# Clock_Led_7_thanh_Huynh_Tan_Cuong.net
KiCad netlist of a schematic drawn in Altium Designer
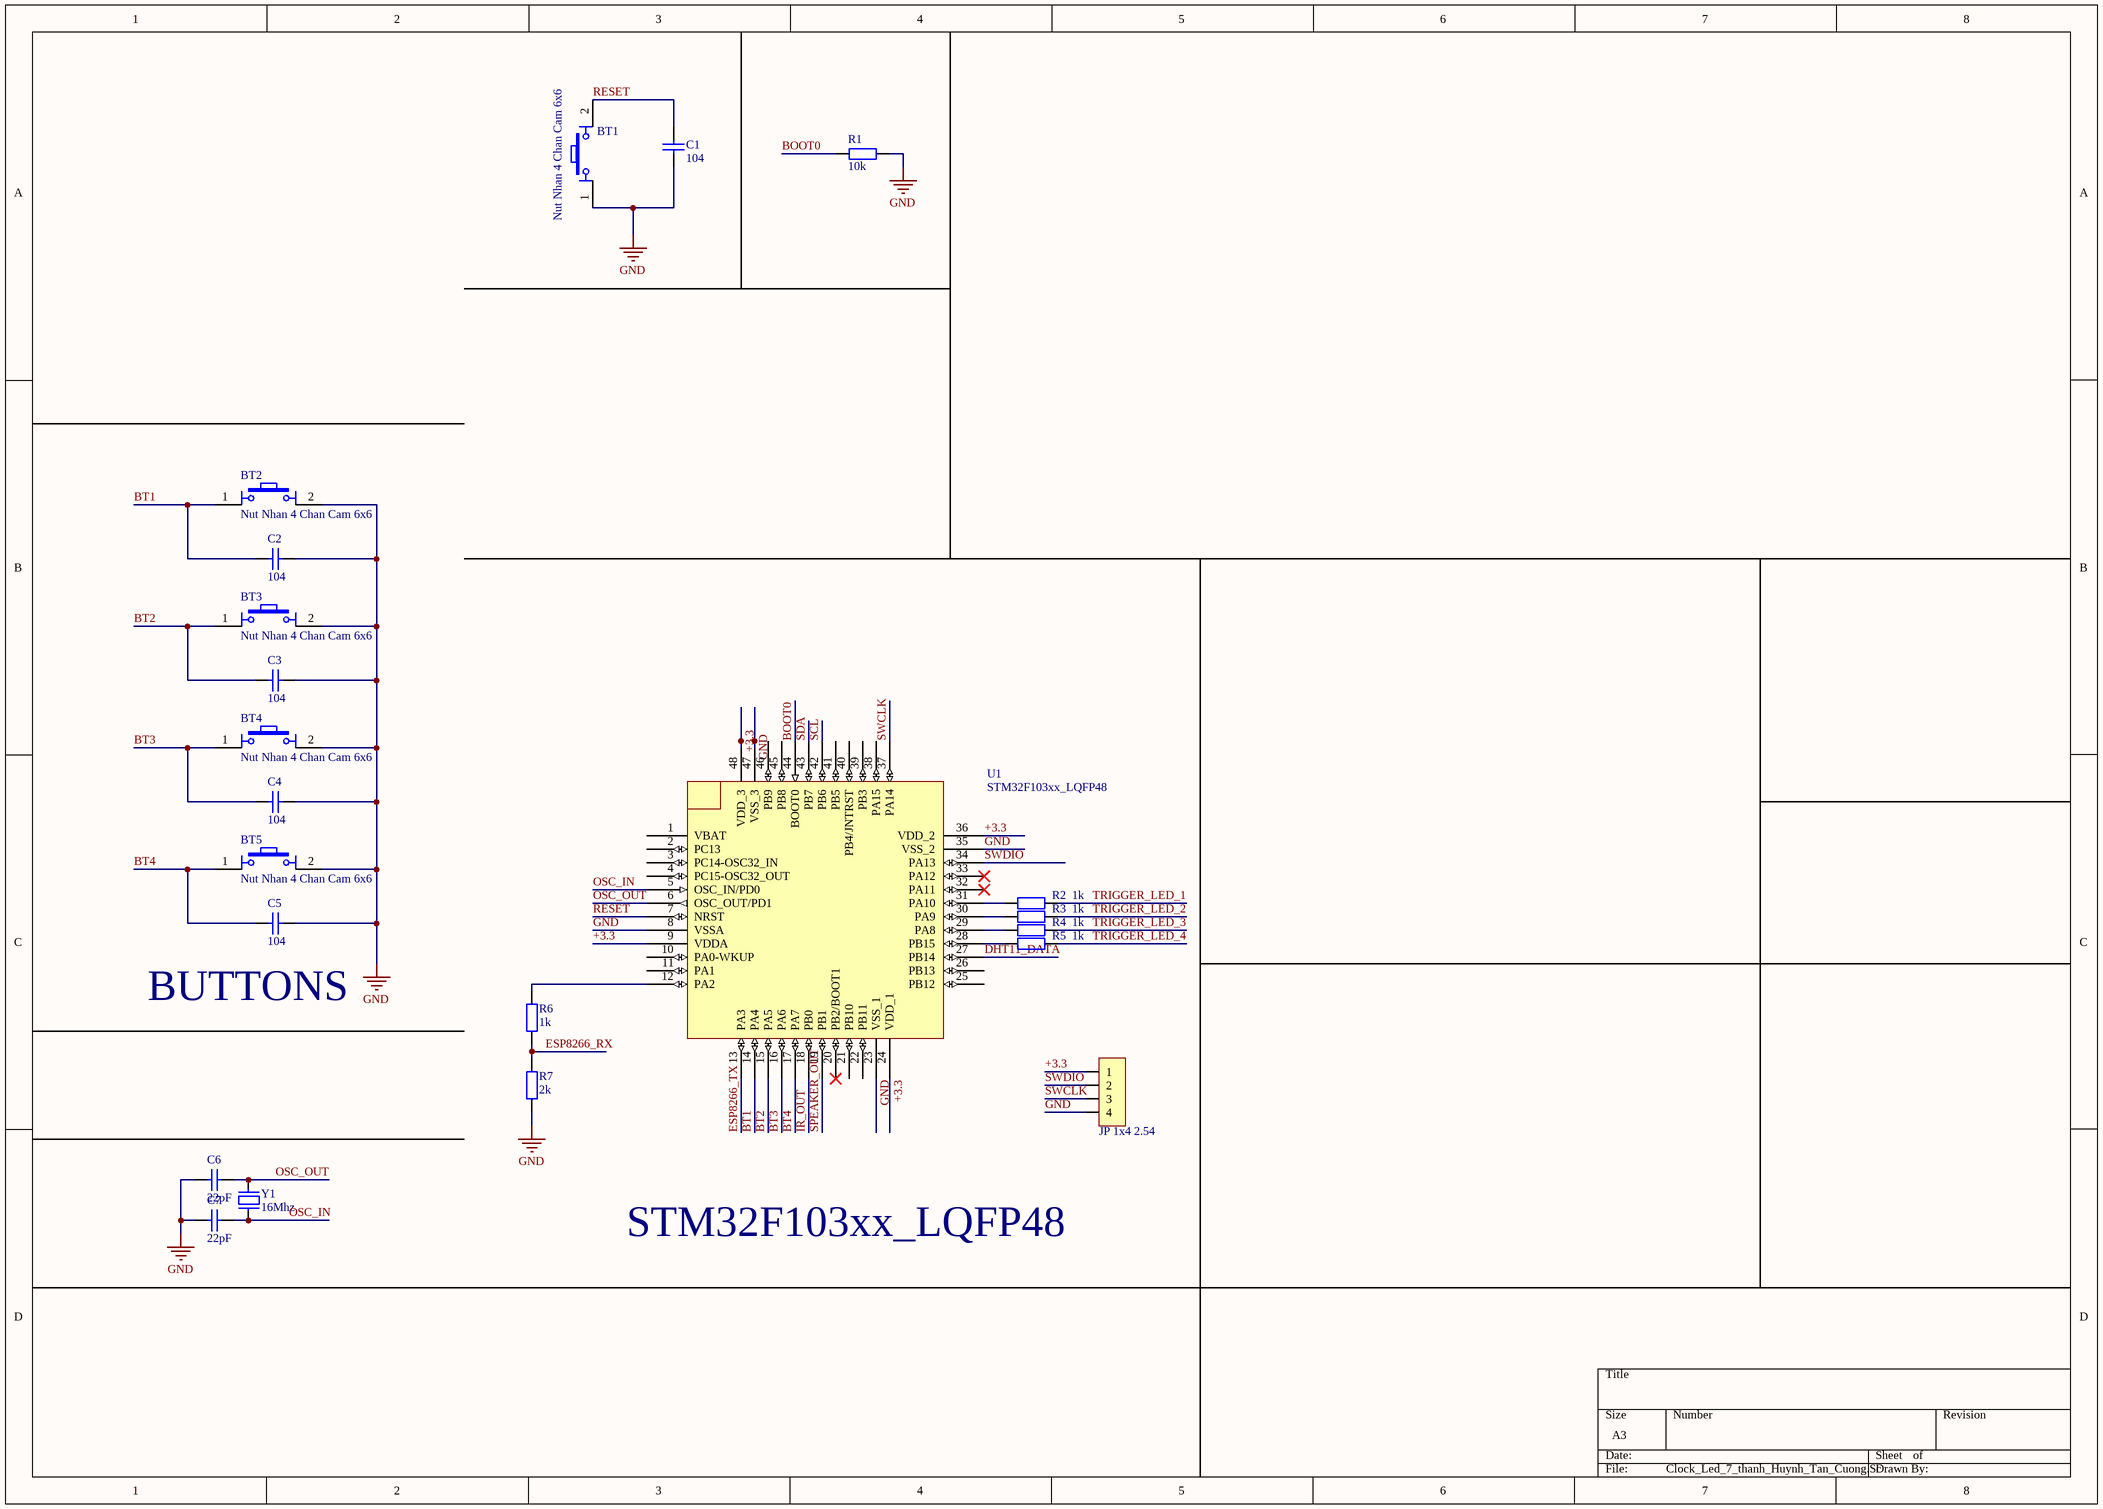
[diagram p0: Clock_Led_7_thanh_Huynh_Tan_Cuong.SchDoc]

(export (version "E")
  (design (tool "Eeschema 10.0.6"))
  (components
    (comp (ref "BT1")
      (value "Nut Nhan 4 Chan Cam 6x6")
      (footprint "Nut Nhan 4 Chan Cam 6x6")
      (description "Nut Nhan 4 Chan 6x6mm")
      (libsource (lib "") (part "Nut Nhan 4 Chan Cam 6x6_1"))
    )
    (comp (ref "BT2")
      (value "Nut Nhan 4 Chan Cam 6x6")
      (footprint "Nut Nhan 4 Chan Cam 6x6")
      (description "Nut Nhan 4 Chan 6x6mm")
      (libsource (lib "Altium_Lib_by_KhueNguyenCreator") (part "Nut Nhan 4 Chan Cam 6x6"))
    )
    (comp (ref "BT3")
      (value "Nut Nhan 4 Chan Cam 6x6")
      (footprint "Nut Nhan 4 Chan Cam 6x6")
      (description "Nut Nhan 4 Chan 6x6mm")
      (libsource (lib "Altium_Lib_by_KhueNguyenCreator") (part "Nut Nhan 4 Chan Cam 6x6"))
    )
    (comp (ref "BT4")
      (value "Nut Nhan 4 Chan Cam 6x6")
      (footprint "Nut Nhan 4 Chan Cam 6x6")
      (description "Nut Nhan 4 Chan 6x6mm")
      (libsource (lib "Altium_Lib_by_KhueNguyenCreator") (part "Nut Nhan 4 Chan Cam 6x6"))
    )
    (comp (ref "BT5")
      (value "Nut Nhan 4 Chan Cam 6x6")
      (footprint "Nut Nhan 4 Chan Cam 6x6")
      (description "Nut Nhan 4 Chan 6x6mm")
      (libsource (lib "Altium_Lib_by_KhueNguyenCreator") (part "Nut Nhan 4 Chan Cam 6x6"))
    )
    (comp (ref "C1")
      (value "104")
      (footprint "tu 0603")
      (description "Dán")
      (libsource (lib "Altium_Lib_by_KhueNguyenCreator") (part "Tu 0603 104 50V 10%"))
    )
    (comp (ref "C2")
      (value "104")
      (footprint "tu 0603")
      (description "Dán")
      (libsource (lib "Altium_Lib_by_KhueNguyenCreator") (part "Tu 0603 104 50V 10%"))
    )
    (comp (ref "C3")
      (value "104")
      (footprint "tu 0603")
      (description "Dán")
      (libsource (lib "Altium_Lib_by_KhueNguyenCreator") (part "Tu 0603 104 50V 10%"))
    )
    (comp (ref "C4")
      (value "104")
      (footprint "tu 0603")
      (description "Dán")
      (libsource (lib "Altium_Lib_by_KhueNguyenCreator") (part "Tu 0603 104 50V 10%"))
    )
    (comp (ref "C5")
      (value "104")
      (footprint "tu 0603")
      (description "Dán")
      (libsource (lib "Altium_Lib_by_KhueNguyenCreator") (part "Tu 0603 104 50V 10%"))
    )
    (comp (ref "C6")
      (value "22pF")
      (footprint "tu 0603")
      (description "Dán")
      (libsource (lib "Altium_Lib_by_KhueNguyenCreator") (part "Tu 0603 22pF 50V 10%"))
    )
    (comp (ref "C7")
      (value "22pF")
      (footprint "tu 0603")
      (description "Dán")
      (libsource (lib "Altium_Lib_by_KhueNguyenCreator") (part "Tu 0603 22pF 50V 10%"))
    )
    (comp (ref "JP1")
      (value "JP 1x4 2.54")
      (footprint "JP 1x4 DC")
      (description "Cắm")
      (libsource (lib "Altium_Lib_by_KhueNguyenCreator") (part "JP 1x4 2.54 Duc Cong"))
    )
    (comp (ref "R1")
      (value "10k")
      (footprint "tro smd 0603")
      (description "Dán")
      (libsource (lib "Altium_Lib_by_KhueNguyenCreator") (part "Tro 0603 1% 10k"))
    )
    (comp (ref "R2")
      (value "1k")
      (footprint "tro smd 0603")
      (description "Dán")
      (libsource (lib "Altium_Lib_by_KhueNguyenCreator") (part "Tro 0603 1% 1k"))
    )
    (comp (ref "R3")
      (value "1k")
      (footprint "tro smd 0603")
      (description "Dán")
      (libsource (lib "Altium_Lib_by_KhueNguyenCreator") (part "Tro 0603 1% 1k"))
    )
    (comp (ref "R4")
      (value "1k")
      (footprint "tro smd 0603")
      (description "Dán")
      (libsource (lib "Altium_Lib_by_KhueNguyenCreator") (part "Tro 0603 1% 1k"))
    )
    (comp (ref "R5")
      (value "1k")
      (footprint "tro smd 0603")
      (description "Dán")
      (libsource (lib "Altium_Lib_by_KhueNguyenCreator") (part "Tro 0603 1% 1k"))
    )
    (comp (ref "R6")
      (value "1k")
      (footprint "tro smd 0603")
      (description "Dán")
      (libsource (lib "Altium_Lib_by_KhueNguyenCreator") (part "Tro 0603 1% 1k"))
    )
    (comp (ref "R7")
      (value "2k")
      (footprint "tro smd 0603")
      (description "Dán")
      (libsource (lib "Altium_Lib_by_KhueNguyenCreator") (part "Tro 0603 5% 2k"))
    )
    (comp (ref "U1")
      (value "STM32F103xx_LQFP48")
      (footprint "STM32_LQPF48")
      (fields (field (name "PUBLISHER") "Altium Limited"))
      (libsource (lib "Altium_Lib_by_KhueNguyenCreator") (part "STM32F103xx_LQFP48"))
    )
    (comp (ref "Y1")
      (value "16Mhz")
      (footprint "Thach Anh 2 chan SMD")
      (description "Crystal For all Crystal 2pin.")
      (libsource (lib "Altium_Lib_by_KhueNguyenCreator") (part "Thach Anh 2 chan SMD"))
    )
  )
  (nets
    (net (code "1") (name "/+3.3") (class "Default")
      (node (ref "JP1") (pin "1") (pinfunction "1_1") (pintype "passive"))
      (node (ref "U1") (pin "24") (pinfunction "VDD_1_24") (pintype "power_in"))
      (node (ref "U1") (pin "36") (pinfunction "VDD_2_36") (pintype "power_in"))
      (node (ref "U1") (pin "48") (pinfunction "VDD_3_48") (pintype "power_in"))
      (node (ref "U1") (pin "9") (pinfunction "VDDA_9") (pintype "power_in"))
    )
    (net (code "2") (name "/BOOT0") (class "Default")
      (node (ref "R1") (pin "1") (pinfunction "1_1") (pintype "passive"))
      (node (ref "U1") (pin "44") (pinfunction "BOOT0_44") (pintype "input"))
    )
    (net (code "3") (name "/BT1") (class "Default")
      (node (ref "BT2") (pin "1") (pintype "passive"))
      (node (ref "C2") (pin "1") (pinfunction "1_1") (pintype "passive"))
      (node (ref "U1") (pin "14") (pinfunction "PA4_14") (pintype "bidirectional"))
    )
    (net (code "4") (name "/BT2") (class "Default")
      (node (ref "BT3") (pin "1") (pintype "passive"))
      (node (ref "C3") (pin "1") (pinfunction "1_1") (pintype "passive"))
      (node (ref "U1") (pin "15") (pinfunction "PA5_15") (pintype "bidirectional"))
    )
    (net (code "5") (name "/BT3") (class "Default")
      (node (ref "BT4") (pin "1") (pintype "passive"))
      (node (ref "C4") (pin "1") (pinfunction "1_1") (pintype "passive"))
      (node (ref "U1") (pin "16") (pinfunction "PA6_16") (pintype "bidirectional"))
    )
    (net (code "6") (name "/BT4") (class "Default")
      (node (ref "BT5") (pin "1") (pintype "passive"))
      (node (ref "C5") (pin "1") (pinfunction "1_1") (pintype "passive"))
      (node (ref "U1") (pin "17") (pinfunction "PA7_17") (pintype "bidirectional"))
    )
    (net (code "7") (name "/DHT11_DATA") (class "Default")
      (node (ref "U1") (pin "27") (pinfunction "PB14_27") (pintype "bidirectional"))
    )
    (net (code "8") (name "/ESP8266_RX") (class "Default")
      (node (ref "R6") (pin "1") (pinfunction "1_1") (pintype "passive"))
      (node (ref "R7") (pin "2") (pinfunction "2_2") (pintype "passive"))
    )
    (net (code "9") (name "/ESP8266_TX") (class "Default")
      (node (ref "U1") (pin "13") (pinfunction "PA3_13") (pintype "bidirectional"))
    )
    (net (code "10") (name "/IR_OUT") (class "Default")
      (node (ref "U1") (pin "18") (pinfunction "PB0_18") (pintype "bidirectional"))
    )
    (net (code "11") (name "/OSC_IN") (class "Default")
      (node (ref "C7") (pin "1") (pinfunction "1_1") (pintype "passive"))
      (node (ref "U1") (pin "5") (pinfunction "OSC_IN/PD0_5") (pintype "input"))
      (node (ref "Y1") (pin "1") (pinfunction "1_1") (pintype "passive"))
    )
    (net (code "12") (name "/OSC_OUT") (class "Default")
      (node (ref "C6") (pin "1") (pinfunction "1_1") (pintype "passive"))
      (node (ref "U1") (pin "6") (pinfunction "OSC_OUT/PD1_6") (pintype "output"))
      (node (ref "Y1") (pin "2") (pinfunction "2_2") (pintype "passive"))
    )
    (net (code "13") (name "/RESET") (class "Default")
      (node (ref "BT1") (pin "2") (pintype "passive"))
      (node (ref "C1") (pin "1") (pinfunction "1_1") (pintype "passive"))
      (node (ref "U1") (pin "7") (pinfunction "NRST_7") (pintype "bidirectional"))
    )
    (net (code "14") (name "/SCL") (class "Default")
      (node (ref "U1") (pin "42") (pinfunction "PB6_42") (pintype "bidirectional"))
    )
    (net (code "15") (name "/SDA") (class "Default")
      (node (ref "U1") (pin "43") (pinfunction "PB7_43") (pintype "bidirectional"))
    )
    (net (code "16") (name "/SPEAKER_OUT") (class "Default")
      (node (ref "U1") (pin "19") (pinfunction "PB1_19") (pintype "bidirectional"))
    )
    (net (code "17") (name "/SWCLK") (class "Default")
      (node (ref "JP1") (pin "3") (pinfunction "3_3") (pintype "passive"))
      (node (ref "U1") (pin "37") (pinfunction "PA14_37") (pintype "bidirectional"))
    )
    (net (code "18") (name "/SWDIO") (class "Default")
      (node (ref "JP1") (pin "2") (pinfunction "2_2") (pintype "passive"))
      (node (ref "U1") (pin "34") (pinfunction "PA13_34") (pintype "bidirectional"))
    )
    (net (code "19") (name "/TRIGGER_LED_1") (class "Default")
      (node (ref "R2") (pin "2") (pinfunction "2_2") (pintype "passive"))
    )
    (net (code "20") (name "/TRIGGER_LED_2") (class "Default")
      (node (ref "R3") (pin "2") (pinfunction "2_2") (pintype "passive"))
    )
    (net (code "21") (name "/TRIGGER_LED_3") (class "Default")
      (node (ref "R4") (pin "2") (pinfunction "2_2") (pintype "passive"))
    )
    (net (code "22") (name "/TRIGGER_LED_4") (class "Default")
      (node (ref "R5") (pin "2") (pinfunction "2_2") (pintype "passive"))
    )
    (net (code "23") (name "GND") (class "Default")
      (node (ref "BT1") (pin "1") (pintype "passive"))
      (node (ref "BT2") (pin "2") (pintype "passive"))
      (node (ref "BT3") (pin "2") (pintype "passive"))
      (node (ref "BT4") (pin "2") (pintype "passive"))
      (node (ref "BT5") (pin "2") (pintype "passive"))
      (node (ref "C1") (pin "2") (pinfunction "2_2") (pintype "passive"))
      (node (ref "C2") (pin "2") (pinfunction "2_2") (pintype "passive"))
      (node (ref "C3") (pin "2") (pinfunction "2_2") (pintype "passive"))
      (node (ref "C4") (pin "2") (pinfunction "2_2") (pintype "passive"))
      (node (ref "C5") (pin "2") (pinfunction "2_2") (pintype "passive"))
      (node (ref "C6") (pin "2") (pinfunction "2_2") (pintype "passive"))
      (node (ref "C7") (pin "2") (pinfunction "2_2") (pintype "passive"))
      (node (ref "JP1") (pin "4") (pinfunction "4_4") (pintype "passive"))
      (node (ref "R1") (pin "2") (pinfunction "2_2") (pintype "passive"))
      (node (ref "R7") (pin "1") (pinfunction "1_1") (pintype "passive"))
      (node (ref "U1") (pin "23") (pinfunction "VSS_1_23") (pintype "power_in"))
      (node (ref "U1") (pin "35") (pinfunction "VSS_2_35") (pintype "power_in"))
      (node (ref "U1") (pin "47") (pinfunction "VSS_3_47") (pintype "power_in"))
      (node (ref "U1") (pin "8") (pinfunction "VSSA_8") (pintype "power_in"))
    )
    (net (code "24") (name "Net-(U1-PA2)") (class "Default")
      (node (ref "R6") (pin "2") (pinfunction "2_2") (pintype "passive"))
      (node (ref "U1") (pin "12") (pinfunction "PA2_12") (pintype "bidirectional"))
    )
    (net (code "25") (name "Net-(U1-PA8)") (class "Default")
      (node (ref "R4") (pin "1") (pinfunction "1_1") (pintype "passive"))
      (node (ref "U1") (pin "29") (pinfunction "PA8_29") (pintype "bidirectional"))
    )
    (net (code "26") (name "Net-(U1-PA9)") (class "Default")
      (node (ref "R3") (pin "1") (pinfunction "1_1") (pintype "passive"))
      (node (ref "U1") (pin "30") (pinfunction "PA9_30") (pintype "bidirectional"))
    )
    (net (code "27") (name "Net-(U1-PA10)") (class "Default")
      (node (ref "R2") (pin "1") (pinfunction "1_1") (pintype "passive"))
      (node (ref "U1") (pin "31") (pinfunction "PA10_31") (pintype "bidirectional"))
    )
    (net (code "28") (name "Net-(U1-PB15)") (class "Default")
      (node (ref "R5") (pin "1") (pinfunction "1_1") (pintype "passive"))
      (node (ref "U1") (pin "28") (pinfunction "PB15_28") (pintype "bidirectional"))
    )
    (net (code "29") (name "unconnected-(U1-PA0-WKUP-Pad10)") (class "Default")
      (node (ref "U1") (pin "10") (pinfunction "PA0-WKUP_10") (pintype "bidirectional"))
    )
    (net (code "30") (name "unconnected-(U1-PA1-Pad11)") (class "Default")
      (node (ref "U1") (pin "11") (pinfunction "PA1_11") (pintype "bidirectional"))
    )
    (net (code "31") (name "unconnected-(U1-PA11-Pad32)") (class "Default")
      (node (ref "U1") (pin "32") (pinfunction "PA11_32") (pintype "bidirectional+no_connect"))
    )
    (net (code "32") (name "unconnected-(U1-PA12-Pad33)") (class "Default")
      (node (ref "U1") (pin "33") (pinfunction "PA12_33") (pintype "bidirectional+no_connect"))
    )
    (net (code "33") (name "unconnected-(U1-PA15-Pad38)") (class "Default")
      (node (ref "U1") (pin "38") (pinfunction "PA15_38") (pintype "bidirectional"))
    )
    (net (code "34") (name "unconnected-(U1-PB2{slash}BOOT1-Pad20)") (class "Default")
      (node (ref "U1") (pin "20") (pinfunction "PB2/BOOT1_20") (pintype "bidirectional+no_connect"))
    )
    (net (code "35") (name "unconnected-(U1-PB3-Pad39)") (class "Default")
      (node (ref "U1") (pin "39") (pinfunction "PB3_39") (pintype "bidirectional"))
    )
    (net (code "36") (name "unconnected-(U1-PB4{slash}JNTRST-Pad40)") (class "Default")
      (node (ref "U1") (pin "40") (pinfunction "PB4/JNTRST_40") (pintype "bidirectional"))
    )
    (net (code "37") (name "unconnected-(U1-PB5-Pad41)") (class "Default")
      (node (ref "U1") (pin "41") (pinfunction "PB5_41") (pintype "bidirectional"))
    )
    (net (code "38") (name "unconnected-(U1-PB8-Pad45)") (class "Default")
      (node (ref "U1") (pin "45") (pinfunction "PB8_45") (pintype "bidirectional"))
    )
    (net (code "39") (name "unconnected-(U1-PB9-Pad46)") (class "Default")
      (node (ref "U1") (pin "46") (pinfunction "PB9_46") (pintype "bidirectional"))
    )
    (net (code "40") (name "unconnected-(U1-PB10-Pad21)") (class "Default")
      (node (ref "U1") (pin "21") (pinfunction "PB10_21") (pintype "bidirectional"))
    )
    (net (code "41") (name "unconnected-(U1-PB11-Pad22)") (class "Default")
      (node (ref "U1") (pin "22") (pinfunction "PB11_22") (pintype "bidirectional"))
    )
    (net (code "42") (name "unconnected-(U1-PB12-Pad25)") (class "Default")
      (node (ref "U1") (pin "25") (pinfunction "PB12_25") (pintype "bidirectional"))
    )
    (net (code "43") (name "unconnected-(U1-PB13-Pad26)") (class "Default")
      (node (ref "U1") (pin "26") (pinfunction "PB13_26") (pintype "bidirectional"))
    )
    (net (code "44") (name "unconnected-(U1-PC13-Pad2)") (class "Default")
      (node (ref "U1") (pin "2") (pinfunction "PC13_2") (pintype "bidirectional"))
    )
    (net (code "45") (name "unconnected-(U1-PC14-OSC32_IN-Pad3)") (class "Default")
      (node (ref "U1") (pin "3") (pinfunction "PC14-OSC32_IN_3") (pintype "bidirectional"))
    )
    (net (code "46") (name "unconnected-(U1-PC15-OSC32_OUT-Pad4)") (class "Default")
      (node (ref "U1") (pin "4") (pinfunction "PC15-OSC32_OUT_4") (pintype "bidirectional"))
    )
    (net (code "47") (name "unconnected-(U1-VBAT-Pad1)") (class "Default")
      (node (ref "U1") (pin "1") (pinfunction "VBAT_1") (pintype "power_in"))
    )
  )
)
